# CC110L.net
KiCad netlist of a schematic drawn in Altium Designer
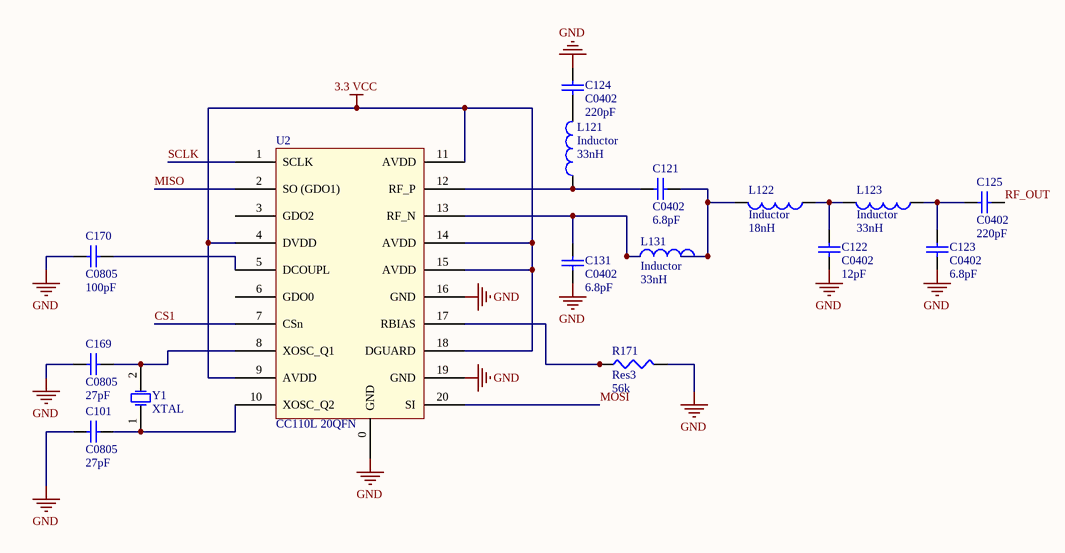
[diagram p0: CC110L.SchDoc]

(export (version "E")
  (design (tool "Eeschema 10.0.6"))
  (components
    (comp (ref "C101")
      (value "C0805")
      (footprint "0805")
      (description "Ceramic Chip Capacitor - Standard")
      (fields (field (name "ALTIUM_VALUE") "27pF") (field (name "PUBLISHER") "Altium Limited"))
      (libsource (lib "KEMET Chip Capacitor") (part "C0805"))
    )
    (comp (ref "C121")
      (value "C0402")
      (footprint "0402")
      (description "Ceramic Chip Capacitor - Standard")
      (fields (field (name "ALTIUM_VALUE") "6.8pF") (field (name "PUBLISHER") "Altium Limited"))
      (libsource (lib "KEMET Chip Capacitor") (part "C0402"))
    )
    (comp (ref "C122")
      (value "C0402")
      (footprint "0402")
      (description "Ceramic Chip Capacitor - Standard")
      (fields (field (name "ALTIUM_VALUE") "12pF") (field (name "PUBLISHER") "Altium Limited"))
      (libsource (lib "KEMET Chip Capacitor") (part "C0402"))
    )
    (comp (ref "C123")
      (value "C0402")
      (footprint "0402")
      (description "Ceramic Chip Capacitor - Standard")
      (fields (field (name "ALTIUM_VALUE") "6.8pF") (field (name "PUBLISHER") "Altium Limited"))
      (libsource (lib "KEMET Chip Capacitor") (part "C0402"))
    )
    (comp (ref "C124")
      (value "C0402")
      (footprint "0402")
      (description "Ceramic Chip Capacitor - Standard")
      (fields (field (name "ALTIUM_VALUE") "220pF") (field (name "PUBLISHER") "Altium Limited"))
      (libsource (lib "KEMET Chip Capacitor") (part "C0402"))
    )
    (comp (ref "C125")
      (value "C0402")
      (footprint "0402")
      (description "Ceramic Chip Capacitor - Standard")
      (fields (field (name "ALTIUM_VALUE") "220pF") (field (name "PUBLISHER") "Altium Limited"))
      (libsource (lib "KEMET Chip Capacitor") (part "C0402"))
    )
    (comp (ref "C131")
      (value "C0402")
      (footprint "0402")
      (description "Ceramic Chip Capacitor - Standard")
      (fields (field (name "ALTIUM_VALUE") "6.8pF") (field (name "PUBLISHER") "Altium Limited"))
      (libsource (lib "KEMET Chip Capacitor") (part "C0402"))
    )
    (comp (ref "C169")
      (value "C0805")
      (footprint "0805")
      (description "Ceramic Chip Capacitor - Standard")
      (fields (field (name "ALTIUM_VALUE") "27pF") (field (name "PUBLISHER") "Altium Limited"))
      (libsource (lib "KEMET Chip Capacitor") (part "C0805"))
    )
    (comp (ref "C170")
      (value "C0805")
      (footprint "0805")
      (description "Ceramic Chip Capacitor - Standard")
      (fields (field (name "ALTIUM_VALUE") "100pF") (field (name "PUBLISHER") "Altium Limited"))
      (libsource (lib "KEMET Chip Capacitor") (part "C0805"))
    )
    (comp (ref "L121")
      (value "Inductor")
      (footprint "0402-A")
      (fields (field (name "ALTIUM_VALUE") "33nH") (field (name "PUBLISHER") "Altium Limited"))
      (libsource (lib "Miscellaneous Devices") (part "Inductor"))
    )
    (comp (ref "L122")
      (value "Inductor")
      (footprint "0402-A")
      (fields (field (name "ALTIUM_VALUE") "18nH") (field (name "PUBLISHER") "Altium Limited"))
      (libsource (lib "Miscellaneous Devices") (part "Inductor"))
    )
    (comp (ref "L123")
      (value "Inductor")
      (footprint "0402-A")
      (fields (field (name "ALTIUM_VALUE") "33nH") (field (name "PUBLISHER") "Altium Limited"))
      (libsource (lib "Miscellaneous Devices") (part "Inductor"))
    )
    (comp (ref "L131")
      (value "Inductor")
      (footprint "0402-A")
      (fields (field (name "ALTIUM_VALUE") "33nH") (field (name "PUBLISHER") "Altium Limited"))
      (libsource (lib "Miscellaneous Devices") (part "Inductor"))
    )
    (comp (ref "R171")
      (value "Res3")
      (footprint "J1-0603")
      (description "Resistor")
      (fields (field (name "ALTIUM_VALUE") "56k") (field (name "PUBLISHER") "Altium Limited"))
      (libsource (lib "Miscellaneous Devices") (part "Res3"))
    )
    (comp (ref "U2")
      (value "CC110L 20QFN")
      (footprint "20QFN")
      (libsource (lib "CC110L_20QFN") (part "CC110L 20QFN"))
    )
    (comp (ref "Y1")
      (value "XTAL")
      (footprint "R38")
      (description "Crystal Oscillator")
      (fields (field (name "PUBLISHER") "Altium Limited"))
      (libsource (lib "Miscellaneous Devices") (part "XTAL"))
    )
  )
  (nets
    (net (code "1") (name "/CS1") (class "Default")
      (node (ref "U2") (pin "7") (pinfunction "CSn_7") (pintype "passive"))
    )
    (net (code "2") (name "/MISO") (class "Default")
      (node (ref "U2") (pin "2") (pinfunction "SO_(GDO1)_2") (pintype "passive"))
    )
    (net (code "3") (name "/MOSI") (class "Default")
      (node (ref "U2") (pin "20") (pinfunction "SI_20") (pintype "passive"))
    )
    (net (code "4") (name "/RF_OUT") (class "Default")
      (node (ref "C125") (pin "2") (pinfunction "2_2") (pintype "passive"))
    )
    (net (code "5") (name "/SCLK") (class "Default")
      (node (ref "U2") (pin "1") (pinfunction "SCLK_1") (pintype "passive"))
    )
    (net (code "6") (name "3.3 VCC") (class "Default")
      (node (ref "U2") (pin "11") (pinfunction "AVDD_11") (pintype "passive"))
      (node (ref "U2") (pin "14") (pinfunction "AVDD_14") (pintype "passive"))
      (node (ref "U2") (pin "15") (pinfunction "AVDD_15") (pintype "passive"))
      (node (ref "U2") (pin "18") (pinfunction "DGUARD_18") (pintype "passive"))
      (node (ref "U2") (pin "4") (pinfunction "DVDD_4") (pintype "passive"))
      (node (ref "U2") (pin "9") (pinfunction "AVDD_9") (pintype "passive"))
    )
    (net (code "7") (name "GND") (class "Default")
      (node (ref "C101") (pin "1") (pinfunction "1_1") (pintype "passive"))
      (node (ref "C122") (pin "1") (pinfunction "1_1") (pintype "passive"))
      (node (ref "C123") (pin "1") (pinfunction "1_1") (pintype "passive"))
      (node (ref "C124") (pin "2") (pinfunction "2_2") (pintype "passive"))
      (node (ref "C131") (pin "1") (pinfunction "1_1") (pintype "passive"))
      (node (ref "C169") (pin "1") (pinfunction "1_1") (pintype "passive"))
      (node (ref "C170") (pin "1") (pinfunction "1_1") (pintype "passive"))
      (node (ref "R171") (pin "2") (pinfunction "2_2") (pintype "passive"))
      (node (ref "U2") (pin "0") (pinfunction "GND_0") (pintype "passive"))
      (node (ref "U2") (pin "16") (pinfunction "GND_16") (pintype "passive"))
      (node (ref "U2") (pin "19") (pinfunction "GND_19") (pintype "passive"))
    )
    (net (code "8") (name "Net-(C121-Pad2)") (class "Default")
      (node (ref "C121") (pin "2") (pinfunction "2_2") (pintype "passive"))
      (node (ref "L122") (pin "2") (pinfunction "2_2") (pintype "passive"))
      (node (ref "L131") (pin "2") (pinfunction "2_2") (pintype "passive"))
    )
    (net (code "9") (name "Net-(C122-Pad2)") (class "Default")
      (node (ref "C122") (pin "2") (pinfunction "2_2") (pintype "passive"))
      (node (ref "L122") (pin "1") (pinfunction "1_1") (pintype "passive"))
      (node (ref "L123") (pin "2") (pinfunction "2_2") (pintype "passive"))
    )
    (net (code "10") (name "Net-(C123-Pad2)") (class "Default")
      (node (ref "C123") (pin "2") (pinfunction "2_2") (pintype "passive"))
      (node (ref "C125") (pin "1") (pinfunction "1_1") (pintype "passive"))
      (node (ref "L123") (pin "1") (pinfunction "1_1") (pintype "passive"))
    )
    (net (code "11") (name "Net-(C124-Pad1)") (class "Default")
      (node (ref "C124") (pin "1") (pinfunction "1_1") (pintype "passive"))
      (node (ref "L121") (pin "2") (pinfunction "2_2") (pintype "passive"))
    )
    (net (code "12") (name "Net-(U2-DCOUPL)") (class "Default")
      (node (ref "C170") (pin "2") (pinfunction "2_2") (pintype "passive"))
      (node (ref "U2") (pin "5") (pinfunction "DCOUPL_5") (pintype "passive"))
    )
    (net (code "13") (name "Net-(U2-RBIAS)") (class "Default")
      (node (ref "R171") (pin "1") (pinfunction "1_1") (pintype "passive"))
      (node (ref "U2") (pin "17") (pinfunction "RBIAS_17") (pintype "passive"))
    )
    (net (code "14") (name "Net-(U2-RF_N)") (class "Default")
      (node (ref "C131") (pin "2") (pinfunction "2_2") (pintype "passive"))
      (node (ref "L131") (pin "1") (pinfunction "1_1") (pintype "passive"))
      (node (ref "U2") (pin "13") (pinfunction "RF_N_13") (pintype "passive"))
    )
    (net (code "15") (name "Net-(U2-RF_P)") (class "Default")
      (node (ref "C121") (pin "1") (pinfunction "1_1") (pintype "passive"))
      (node (ref "L121") (pin "1") (pinfunction "1_1") (pintype "passive"))
      (node (ref "U2") (pin "12") (pinfunction "RF_P_12") (pintype "passive"))
    )
    (net (code "16") (name "Net-(U2-XOSC_Q1)") (class "Default")
      (node (ref "C169") (pin "2") (pinfunction "2_2") (pintype "passive"))
      (node (ref "U2") (pin "8") (pinfunction "XOSC_Q1_8") (pintype "passive"))
      (node (ref "Y1") (pin "2") (pinfunction "OSC2_2") (pintype "passive"))
    )
    (net (code "17") (name "Net-(U2-XOSC_Q2)") (class "Default")
      (node (ref "C101") (pin "2") (pinfunction "2_2") (pintype "passive"))
      (node (ref "U2") (pin "10") (pinfunction "XOSC_Q2_10") (pintype "passive"))
      (node (ref "Y1") (pin "1") (pinfunction "OSC1_1") (pintype "passive"))
    )
    (net (code "18") (name "unconnected-(U2-GDO0-Pad6)") (class "Default")
      (node (ref "U2") (pin "6") (pinfunction "GDO0_6") (pintype "passive"))
    )
    (net (code "19") (name "unconnected-(U2-GDO2-Pad3)") (class "Default")
      (node (ref "U2") (pin "3") (pinfunction "GDO2_3") (pintype "passive"))
    )
  )
)
